# 06-Power_B.net
KiCad netlist of a schematic drawn in Altium Designer
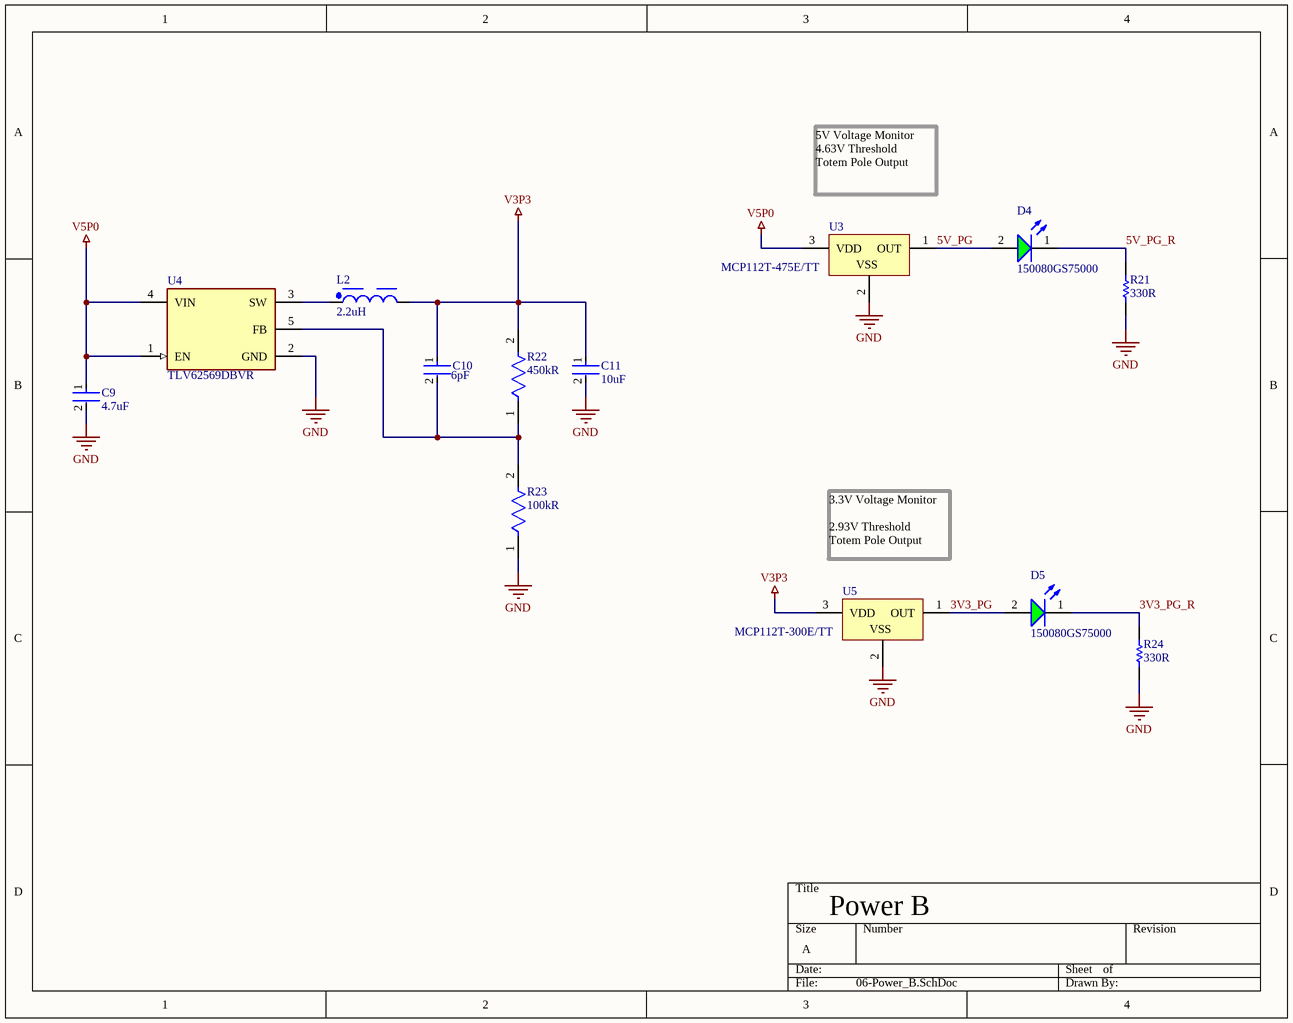
[diagram p0: 06-Power_B.SchDoc]

(export (version "E")
  (design (tool "Eeschema 10.0.6"))
  (components
    (comp (ref "C9")
      (value "4.7uF")
      (footprint "FP-CC0805-0_85-MFG")
      (description "CC0805MKX7R8BB475\r\nCAP CER 4.7UF 25V X7R 0805")
      (fields
        (field (name "MANUFACTURER") "Yageo")
        (field (name "MANUFACTURER PART NUMBER") "CC0805MKX7R8BB475")
      )
      (libsource (lib "Altium Content Vault") (part "11868f565c42a9108669ba33697ecf6"))
    )
    (comp (ref "C10")
      (value "6pF")
      (footprint "FP-CBR08C-MFG")
      (description "CAP CER 6PF 250V C0G/NP0 0805")
      (fields
        (field (name "MANUFACTURER PART NUMBER") "CBR08C609CAGAC")
        (field (name "OCTOPART") "https://octopart.com/cbr08c609cagac-kemet-23841672")
      )
      (libsource (lib "Altium Content Vault") (part "11868f565c42a9108669ba33697ecf6"))
    )
    (comp (ref "C11")
      (value "10uF")
      (footprint "FP-C0805C-DG-MFG")
      (description "CAP CER 10UF 10V X5R 0805")
      (fields (field (name "TOLERANCE") "10%") (field (name "MANUFACTURER PART NUMBER") "C0805C106K8PACTU"))
      (libsource (lib "Altium Content Vault") (part "11868f565c42a9108669ba33697ecf6"))
    )
    (comp (ref "D4")
      (value "150080GS75000")
      (footprint "WL-SMCW_0805_150080xx75000")
      (description "LED GREEN CLEAR 0805 SMD")
      (fields (field (name "MANUFACTURER") "Wurth Electronics"))
      (libsource (lib "Altium Content Vault") (part "LED_Green_2A-1K"))
    )
    (comp (ref "D5")
      (value "150080GS75000")
      (footprint "WL-SMCW_0805_150080xx75000")
      (description "LED GREEN CLEAR 0805 SMD")
      (fields (field (name "MANUFACTURER") "Wurth Electronics"))
      (libsource (lib "Altium Content Vault") (part "LED_Green_2A-1K"))
    )
    (comp (ref "L2")
      (value "2.2uH")
      (footprint "WE-TPC_8043")
      (description "Fixed Ind 2.2UH 5.4A 13 Mohm SMD")
      (fields (field (name "TOLERANCE") "30%"))
      (libsource (lib "Altium Content Vault") (part "Inductor - 2"))
    )
    (comp (ref "R21")
      (value "330R")
      (footprint "RESC2013X60X40LL20T25")
      (description "RES SMD 330 OHM 1% 1/8W 0805")
      (fields
        (field (name "MANUFACTURER") "Panasonic")
        (field (name "MANUFACTURER PART NUMBER") "ERJ-6ENF3300V")
      )
      (libsource (lib "Altium Content Vault") (part "RES"))
    )
    (comp (ref "R22")
      (value "450kR")
      (footprint "FP-RT0805-MFG")
      (description "RES SMD 453K OHM 0.1% 1/8W 0805")
      (fields
        (field (name "MANUFACTURER PART NUMBER") "RT0805BRD07453KL")
        (field (name "MANUFACTURER") "Yageo")
      )
      (libsource (lib "Altium Content Vault") (part "1029c3af85768c4190bb7ad29bc67b5"))
    )
    (comp (ref "R23")
      (value "100kR")
      (footprint "FP-RMCF0805-IPC_C")
      (description "100kΩ ±1% 0.125W 0805 Thick Film Chip Resistor AEC-Q200 compliant")
      (fields (field (name "TOLERANCE") "1%"))
      (libsource (lib "Altium Content Vault") (part "1029c3af85768c4190bb7ad29bc67b5"))
    )
    (comp (ref "R24")
      (value "330R")
      (footprint "RESC2013X60X40LL20T25")
      (description "RES SMD 330 OHM 1% 1/8W 0805")
      (fields
        (field (name "MANUFACTURER") "Panasonic")
        (field (name "MANUFACTURER PART NUMBER") "ERJ-6ENF3300V")
      )
      (libsource (lib "Altium Content Vault") (part "RES"))
    )
    (comp (ref "U3")
      (value "MCP112T-475E/TT")
      (footprint "SOT-23-TT3_L")
      (libsource (lib "Altium Content Vault") (part "PM-VLTD-MCP11X-SOT3"))
    )
    (comp (ref "U4")
      (value "TLV62569DBVR")
      (footprint "FP-DBV0005A-MFG")
      (description "IC REG BUCK ADJ 2A SOT23-5")
      (libsource (lib "Altium Content Vault") (part "f8671745ee5fb9a493b385c735b730b"))
    )
    (comp (ref "U5")
      (value "MCP112T-300E/TT")
      (footprint "SOT-23-TT3_L")
      (fields (field (name "MANUFACTURER") "Microchip"))
      (libsource (lib "Altium Content Vault") (part "PM-VLTD-MCP11X-SOT3"))
    )
  )
  (nets
    (net (code "1") (name "/3V3_PG") (class "Default")
      (node (ref "D5") (pin "2") (pinfunction "A_2") (pintype "passive"))
      (node (ref "U5") (pin "1") (pinfunction "OUT_1") (pintype "power_in"))
    )
    (net (code "2") (name "/3V3_PG_R") (class "Default")
      (node (ref "D5") (pin "1") (pinfunction "K_1") (pintype "passive"))
      (node (ref "R24") (pin "2") (pinfunction "2_2") (pintype "passive"))
    )
    (net (code "3") (name "/5V_PG") (class "Default")
      (node (ref "D4") (pin "2") (pinfunction "A_2") (pintype "passive"))
      (node (ref "U3") (pin "1") (pinfunction "OUT_1") (pintype "power_in"))
    )
    (net (code "4") (name "/5V_PG_R") (class "Default")
      (node (ref "D4") (pin "1") (pinfunction "K_1") (pintype "passive"))
      (node (ref "R21") (pin "2") (pinfunction "2_2") (pintype "passive"))
    )
    (net (code "5") (name "GND") (class "Default")
      (node (ref "C11") (pin "2") (pinfunction "2_2") (pintype "passive"))
      (node (ref "C9") (pin "2") (pinfunction "2_2") (pintype "passive"))
      (node (ref "R21") (pin "1") (pinfunction "1_1") (pintype "passive"))
      (node (ref "R23") (pin "1") (pinfunction "1_1") (pintype "passive"))
      (node (ref "R24") (pin "1") (pinfunction "1_1") (pintype "passive"))
      (node (ref "U3") (pin "2") (pinfunction "VSS_2") (pintype "power_in"))
      (node (ref "U4") (pin "2") (pinfunction "GND_2") (pintype "power_in"))
      (node (ref "U5") (pin "2") (pinfunction "VSS_2") (pintype "power_in"))
    )
    (net (code "6") (name "Net-(U4-FB)") (class "Default")
      (node (ref "C10") (pin "2") (pinfunction "2_2") (pintype "passive"))
      (node (ref "R22") (pin "1") (pinfunction "1_1") (pintype "passive"))
      (node (ref "R23") (pin "2") (pinfunction "2_2") (pintype "passive"))
      (node (ref "U4") (pin "5") (pinfunction "FB_5") (pintype "passive"))
    )
    (net (code "7") (name "Net-(U4-SW)") (class "Default")
      (node (ref "L2") (pin "1") (pinfunction "1_1") (pintype "passive"))
      (node (ref "U4") (pin "3") (pinfunction "SW_3") (pintype "power_in"))
    )
    (net (code "8") (name "V3P3") (class "Default")
      (node (ref "C10") (pin "1") (pinfunction "1_1") (pintype "passive"))
      (node (ref "C11") (pin "1") (pinfunction "1_1") (pintype "passive"))
      (node (ref "L2") (pin "2") (pinfunction "2_2") (pintype "passive"))
      (node (ref "R22") (pin "2") (pinfunction "2_2") (pintype "passive"))
      (node (ref "U5") (pin "3") (pinfunction "VDD_3") (pintype "power_in"))
    )
    (net (code "9") (name "V5P0") (class "Default")
      (node (ref "C9") (pin "1") (pinfunction "1_1") (pintype "passive"))
      (node (ref "U3") (pin "3") (pinfunction "VDD_3") (pintype "power_in"))
      (node (ref "U4") (pin "1") (pinfunction "EN_1") (pintype "input"))
      (node (ref "U4") (pin "4") (pinfunction "VIN_4") (pintype "power_in"))
    )
  )
)
